# 5_rf_path.net
KiCad netlist of a schematic drawn in Altium Designer
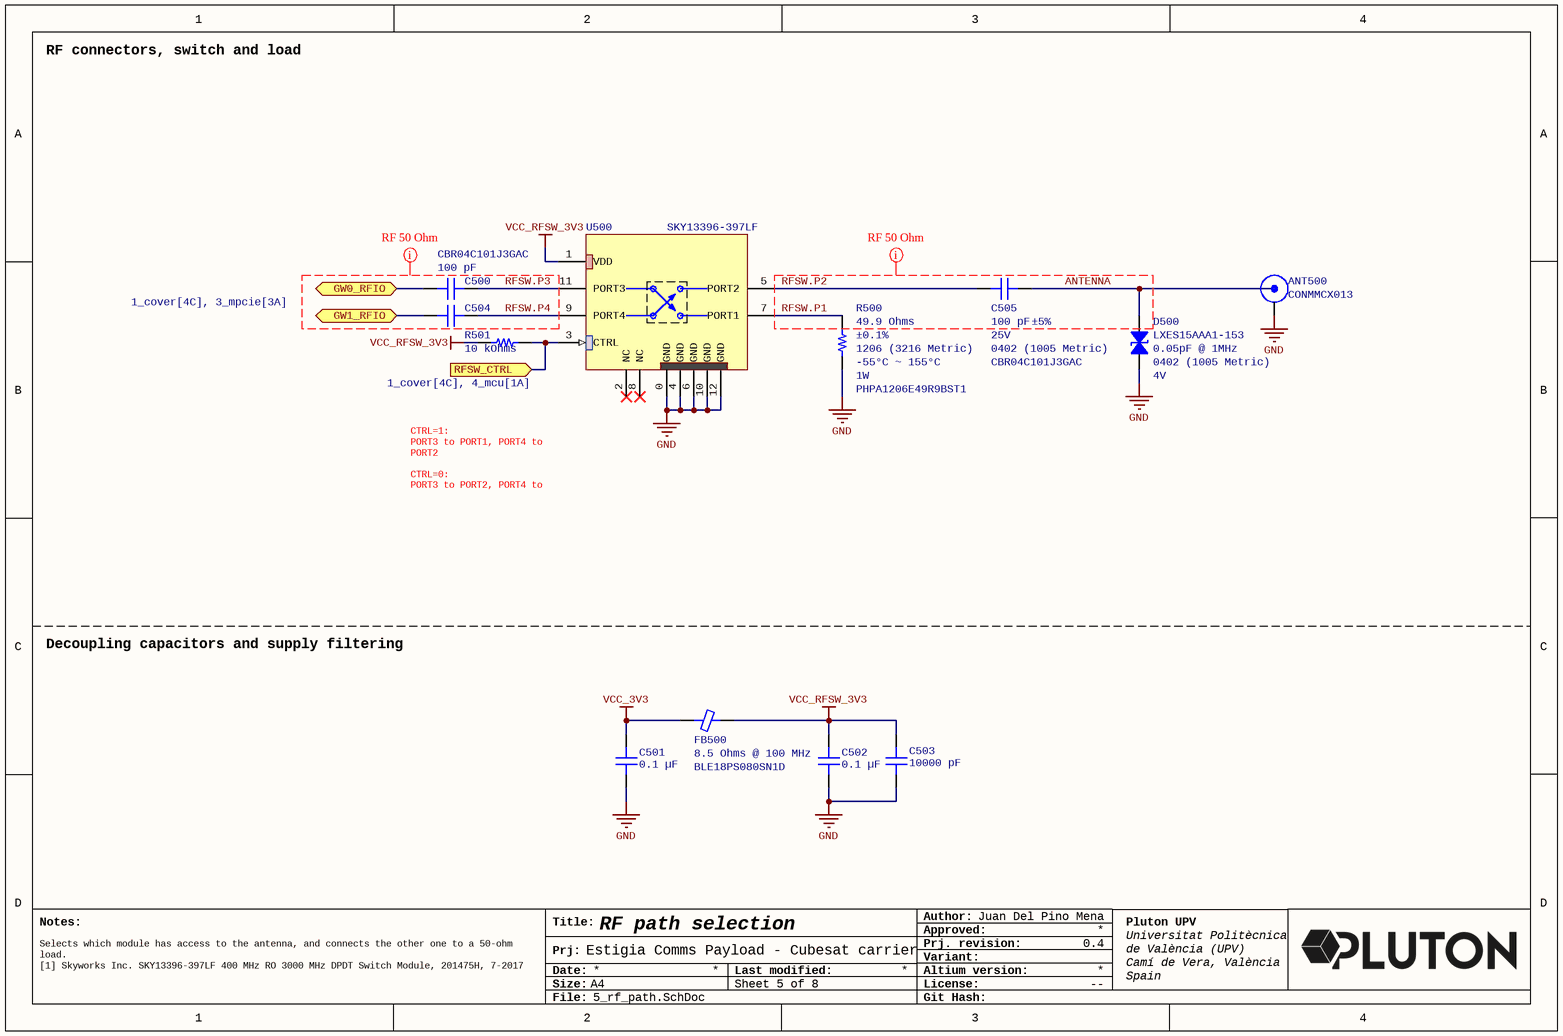
[diagram p0: 5_rf_path.SchDoc]

(export (version "E")
  (design (tool "Eeschema 10.0.6"))
  (components
    (comp (ref "ANT500")
      (value "CONMMCX013")
      (footprint "connectors:CONMMCX013")
      (description "MMCX Jack PCB Cutout Edge Mount Connector 0 to 8.5 GHz operation MMCX (female socket) connection")
      (libsource (lib "connectors") (part "MMCX-CONMMCX013"))
    )
    (comp (ref "C500")
      (value "100 pF")
      (footprint "CAP 0402_1005 RF")
      (description "CAP CER 100PF 25V C0G/NP0 0402")
      (fields
        (field (name "PART NUMBER") "CBR04C101J3GAC")
        (field (name "CAPACITANCE") "100 pF")
        (field (name "MANUFACTURER") "KEMET")
        (field (name "TOLERANCE") "±5%")
      )
      (libsource (lib "Celestial Altium Library - altium_library") (part "Capacitor"))
    )
    (comp (ref "C501")
      (value "0.1 µF")
      (footprint "CAP 0402_1005")
      (description "CAP CER 0402 0.1UF 16V X7R 10%")
      (fields (field (name "PART NUMBER") "C0402C104K4RECAUTO") (field (name "MANUFACTURER") "KEMET"))
      (libsource (lib "Celestial Altium Library - altium_library") (part "Capacitor"))
    )
    (comp (ref "C502")
      (value "0.1 µF")
      (footprint "CAP 0402_1005")
      (description "CAP CER 0402 0.1UF 16V X7R 10%")
      (fields (field (name "PART NUMBER") "C0402C104K4RECAUTO") (field (name "MANUFACTURER") "KEMET"))
      (libsource (lib "Celestial Altium Library - altium_library") (part "Capacitor"))
    )
    (comp (ref "C503")
      (value "10000 pF")
      (footprint "CAP 0402_1005")
      (description "CAP CER 10000PF 25V C0G/NP0 0402")
      (fields
        (field (name "PART NUMBER") "GRM1555C1E103JE01J")
        (field (name "MANUFACTURER") "Murata Electronics")
      )
      (libsource (lib "Celestial Altium Library - altium_library") (part "Capacitor"))
    )
    (comp (ref "C504")
      (value "100 pF")
      (footprint "CAP 0402_1005 RF")
      (description "CAP CER 100PF 25V C0G/NP0 0402")
      (fields (field (name "PART NUMBER") "CBR04C101J3GAC") (field (name "MANUFACTURER") "KEMET"))
      (libsource (lib "Celestial Altium Library - altium_library") (part "Capacitor"))
    )
    (comp (ref "C505")
      (value "100 pF")
      (footprint "CAP 0402_1005 RF")
      (description "CAP CER 100PF 25V C0G/NP0 0402")
      (fields
        (field (name "PART NUMBER") "CBR04C101J3GAC")
        (field (name "CAPACITANCE") "100 pF")
        (field (name "DEVICE PACKAGE") "0402 (1005 Metric)")
        (field (name "MANUFACTURER") "KEMET")
        (field (name "TOLERANCE") "±5%")
        (field (name "VOLTAGE - RATED") "25V")
      )
      (libsource (lib "Celestial Altium Library - altium_library") (part "Capacitor"))
    )
    (comp (ref "D500")
      (value "LXES15AAA1-153")
      (footprint "0402")
      (description "TVS DIODE 4V 1005")
      (fields
        (field (name "PART NUMBER") "LXES15AAA1-153")
        (field (name "CAPACITANCE @ FREQUENCY") "0.05pF @ 1MHz")
        (field (name "DEVICE PACKAGE") "0402 (1005 Metric)")
        (field (name "MANUFACTURER") "Murata Electronics")
        (field (name "VOLTAGE - REVERSE STANDOFF (TYP)") "4V")
      )
      (libsource (lib "Celestial Altium Library - altium_library") (part "Diode TVS"))
    )
    (comp (ref "FB500")
      (value "8.5 Ohms @ 100 MHz")
      (footprint "FER 0603_1608")
      (description "FERRITE BEAD 8.5 OHM 0603 1LN")
      (fields
        (field (name "PART NUMBER") "BLE18PS080SN1D")
        (field (name "IMPEDANCE @ FREQUENCY") "8.5 Ohms @ 100 MHz")
        (field (name "MANUFACTURER") "Murata Electronics")
      )
      (libsource (lib "Celestial Altium Library - altium_library") (part "Ferrite Chip"))
    )
    (comp (ref "R500")
      (value "49.9 Ohms")
      (footprint "RES 1206_3216")
      (description "THIN FILM RES SMD 49.9 OHM 0.1%")
      (fields
        (field (name "PART NUMBER") "PHPA1206E49R9BST1")
        (field (name "DEVICE PACKAGE") "1206 (3216 Metric)")
        (field (name "MANUFACTURER") "Vishay Dale Thin Film")
        (field (name "OPERATING TEMPERATURE") "-55°C ~ 155°C")
        (field (name "POWER (WATTS)") "1W")
        (field (name "TOLERANCE") "±0.1%")
      )
      (libsource (lib "Celestial Altium Library - altium_library") (part "Resistor"))
    )
    (comp (ref "R501")
      (value "10 kOhms")
      (footprint "RES 0201_0603")
      (description "RES SMD 10K OHM 1% 1/20W 0201")
      (fields (field (name "PART NUMBER") "AF0201FR-0710KL") (field (name "MANUFACTURER") "Yageo"))
      (libsource (lib "Celestial Altium Library - altium_library") (part "Resistor"))
    )
    (comp (ref "U500")
      (value "SKY13396-397LF")
      (footprint "ics:SKY13396-397LF")
      (description "0.4 to 3.0 GHz DPDT Switch")
      (libsource (lib "rf") (part "SKY13396-397LF"))
    )
  )
  (nets
    (net (code "1") (name "/ANTENNA") (class "Default")
      (node (ref "ANT500") (pin "1") (pinfunction "SIGNAL_1") (pintype "passive"))
      (node (ref "C505") (pin "2") (pinfunction "2_2") (pintype "passive"))
      (node (ref "D500") (pin "2") (pinfunction "2_2") (pintype "passive"))
    )
    (net (code "2") (name "/GW0_RFIO") (class "Default")
      (node (ref "C500") (pin "1") (pinfunction "1_1") (pintype "passive"))
    )
    (net (code "3") (name "/GW1_RFIO") (class "Default")
      (node (ref "C504") (pin "1") (pinfunction "1_1") (pintype "passive"))
    )
    (net (code "4") (name "/RFSW.P1") (class "Default")
      (node (ref "R500") (pin "2") (pinfunction "2_2") (pintype "passive"))
      (node (ref "U500") (pin "7") (pinfunction "PORT1_7") (pintype "passive"))
    )
    (net (code "5") (name "/RFSW.P2") (class "Default")
      (node (ref "C505") (pin "1") (pinfunction "1_1") (pintype "passive"))
      (node (ref "U500") (pin "5") (pinfunction "PORT2_5") (pintype "passive"))
    )
    (net (code "6") (name "/RFSW.P3") (class "Default")
      (node (ref "C500") (pin "2") (pinfunction "2_2") (pintype "passive"))
      (node (ref "U500") (pin "11") (pinfunction "PORT3_11") (pintype "passive"))
    )
    (net (code "7") (name "/RFSW.P4") (class "Default")
      (node (ref "C504") (pin "2") (pinfunction "2_2") (pintype "passive"))
      (node (ref "U500") (pin "9") (pinfunction "PORT4_9") (pintype "passive"))
    )
    (net (code "8") (name "/RFSW_CTRL") (class "Default")
      (node (ref "R501") (pin "1") (pinfunction "1_1") (pintype "passive"))
      (node (ref "U500") (pin "3") (pinfunction "CTRL_3") (pintype "input"))
    )
    (net (code "9") (name "GND") (class "Default")
      (node (ref "ANT500") (pin "2") (pinfunction "GND_2") (pintype "passive"))
      (node (ref "C501") (pin "1") (pinfunction "1_1") (pintype "passive"))
      (node (ref "C502") (pin "1") (pinfunction "1_1") (pintype "passive"))
      (node (ref "C503") (pin "1") (pinfunction "1_1") (pintype "passive"))
      (node (ref "D500") (pin "1") (pinfunction "1_1") (pintype "passive"))
      (node (ref "R500") (pin "1") (pinfunction "1_1") (pintype "passive"))
      (node (ref "U500") (pin "0") (pinfunction "GND_0") (pintype "power_in"))
      (node (ref "U500") (pin "10") (pinfunction "GND_10") (pintype "power_in"))
      (node (ref "U500") (pin "12") (pinfunction "GND_12") (pintype "power_in"))
      (node (ref "U500") (pin "4") (pinfunction "GND_4") (pintype "power_in"))
      (node (ref "U500") (pin "6") (pinfunction "GND_6") (pintype "power_in"))
    )
    (net (code "10") (name "VCC_3V3") (class "Default")
      (node (ref "C501") (pin "2") (pinfunction "2_2") (pintype "passive"))
      (node (ref "FB500") (pin "1") (pinfunction "1_1") (pintype "passive"))
    )
    (net (code "11") (name "VCC_RFSW_3V3") (class "Default")
      (node (ref "C502") (pin "2") (pinfunction "2_2") (pintype "passive"))
      (node (ref "C503") (pin "2") (pinfunction "2_2") (pintype "passive"))
      (node (ref "FB500") (pin "2") (pinfunction "2_2") (pintype "passive"))
      (node (ref "R501") (pin "2") (pinfunction "2_2") (pintype "passive"))
      (node (ref "U500") (pin "1") (pinfunction "VDD_1") (pintype "power_in"))
    )
    (net (code "12") (name "unconnected-(U500-NC-Pad2)") (class "Default")
      (node (ref "U500") (pin "2") (pinfunction "NC_2") (pintype "passive+no_connect"))
    )
    (net (code "13") (name "unconnected-(U500-NC-Pad8)") (class "Default")
      (node (ref "U500") (pin "8") (pinfunction "NC_8") (pintype "passive+no_connect"))
    )
  )
)
